# board.net
KiCad netlist of a schematic drawn in EAGLE
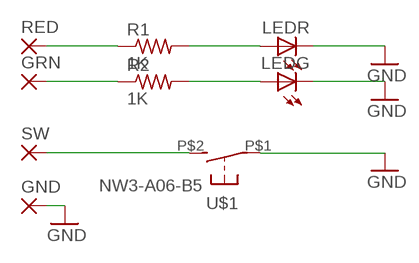
[diagram p0: schematic, sheet 1]

(export (version "E")
  (design (tool "Eeschema 10.0.6"))
  (components
    (comp (ref "GND")
      (value "SMD5")
      (footprint "eagle-import:SMD2,54-5,08")
      (libsource (lib "eagle-import") (part "SMD5"))
    )
    (comp (ref "GRN")
      (value "SMD5")
      (footprint "eagle-import:SMD2,54-5,08")
      (libsource (lib "eagle-import") (part "SMD5"))
    )
    (comp (ref "LEDG")
      (value "LEDCHIP-LED0805")
      (footprint "eagle-import:CHIP-LED0805")
      (libsource (lib "eagle-import") (part "LEDCHIP-LED0805"))
    )
    (comp (ref "LEDR")
      (value "LEDCHIP-LED0805")
      (footprint "eagle-import:CHIP-LED0805")
      (libsource (lib "eagle-import") (part "LEDCHIP-LED0805"))
    )
    (comp (ref "R1")
      (value "1K")
      (footprint "eagle-import:M2012")
      (libsource (lib "eagle-import") (part "R-US_M2012"))
    )
    (comp (ref "R2")
      (value "1K")
      (footprint "eagle-import:M2012")
      (libsource (lib "eagle-import") (part "R-US_M2012"))
    )
    (comp (ref "RED")
      (value "SMD5")
      (footprint "eagle-import:SMD2,54-5,08")
      (libsource (lib "eagle-import") (part "SMD5"))
    )
    (comp (ref "SW")
      (value "SMD5")
      (footprint "eagle-import:SMD2,54-5,08")
      (libsource (lib "eagle-import") (part "SMD5"))
    )
    (comp (ref "U$1")
      (value "NW3-A06-B5")
      (footprint "eagle-import:DTSM-3-R")
      (libsource (lib "eagle-import") (part "NW3-A06-B5"))
    )
  )
  (nets
    (net (code "1") (name "GND") (class "Default")
      (node (ref "GND") (pin "1") (pinfunction "P_1") (pintype "passive"))
      (node (ref "LEDG") (pin "C") (pinfunction "C_C") (pintype "passive"))
      (node (ref "LEDR") (pin "C") (pinfunction "C_C") (pintype "passive"))
      (node (ref "U$1") (pin "P$1") (pinfunction "1_P$1") (pintype "passive"))
    )
    (net (code "2") (name "Net-(GRN-P)") (class "Default")
      (node (ref "GRN") (pin "1") (pinfunction "P_1") (pintype "passive"))
      (node (ref "R2") (pin "1") (pinfunction "1_1") (pintype "passive"))
    )
    (net (code "3") (name "Net-(LEDG-PadA)") (class "Default")
      (node (ref "LEDG") (pin "A") (pinfunction "A_A") (pintype "passive"))
      (node (ref "R2") (pin "2") (pinfunction "2_2") (pintype "passive"))
    )
    (net (code "4") (name "Net-(LEDR-PadA)") (class "Default")
      (node (ref "LEDR") (pin "A") (pinfunction "A_A") (pintype "passive"))
      (node (ref "R1") (pin "2") (pinfunction "2_2") (pintype "passive"))
    )
    (net (code "5") (name "Net-(RED-P)") (class "Default")
      (node (ref "R1") (pin "1") (pinfunction "1_1") (pintype "passive"))
      (node (ref "RED") (pin "1") (pinfunction "P_1") (pintype "passive"))
    )
    (net (code "6") (name "Net-(SW-P)") (class "Default")
      (node (ref "SW") (pin "1") (pinfunction "P_1") (pintype "passive"))
      (node (ref "U$1") (pin "P$2") (pinfunction "2_P$2") (pintype "passive"))
    )
  )
)
